# 2018_PanneauDomotiqueSimple.net
KiCad netlist of a schematic drawn in Altium Designer
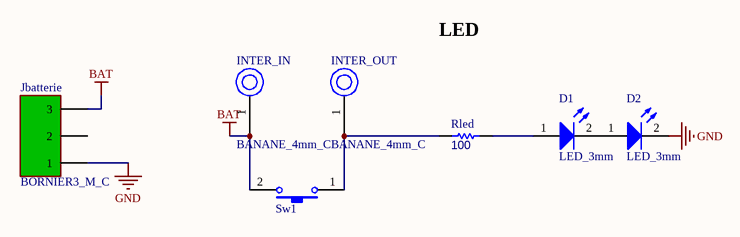
[diagram p0: 2018_PanneauDomotiqueSimple.SchDoc]

(export (version "E")
  (design (tool "Eeschema 10.0.6"))
  (components
    (comp (ref "D1")
      (value "LED_3MM")
      (footprint "LED_3MM")
      (description "LED 3MM - ROUGE/VERTE/JAUNE")
      (fields (field (name "TYPE") "LED_3mm"))
      (libsource (lib "affichage") (part "LED_3MM"))
    )
    (comp (ref "D2")
      (value "LED_3MM")
      (footprint "LED_3MM")
      (description "LED 3MM - ROUGE/VERTE/JAUNE")
      (fields (field (name "TYPE") "LED_3mm"))
      (libsource (lib "affichage") (part "LED_3MM"))
    )
    (comp (ref "INTER_IN")
      (value "DOUILLE BANANE 4mm COUDEE")
      (footprint "DOUILLE_BANANE_4MM_COUDEE")
      (description "DOUILLE BANANE 4 mm COUDEE")
      (fields (field (name "TYPE") "BANANE_4mm_C"))
      (libsource (lib "connecteurs") (part "DOUILLE_BANANE_4mm_COUDEE"))
    )
    (comp (ref "INTER_OUT")
      (value "DOUILLE BANANE 4mm COUDEE")
      (footprint "DOUILLE_BANANE_4MM_COUDEE")
      (description "DOUILLE BANANE 4 mm COUDEE")
      (fields (field (name "TYPE") "BANANE_4mm_C"))
      (libsource (lib "connecteurs") (part "DOUILLE_BANANE_4mm_COUDEE"))
    )
    (comp (ref "Jbatterie")
      (value "BORNIER3 MALE COUDE")
      (footprint "BORNIER3_M_C")
      (description "BORNIER 3 PLOTS MALE COUDE - ENFICHAGE PARALLELE")
      (fields (field (name "TYPE") "BORNIER3_M_C"))
      (libsource (lib "connecteurs") (part "BORNIER3_MALE_COUDE"))
    )
    (comp (ref "Rled")
      (value "100")
      (footprint "RESISTANCE_1/4W")
      (description "RESISTANCE TRAVERSANTE AXIALE 1/4W")
      (fields (field (name "Comment") "RESISTANCE_AXIALE_1/4W"))
      (libsource (lib "composants passifs") (part "RESISTANCE_AXIALE_1/4W"))
    )
    (comp (ref "Sw1")
      (value "BOUTON_POUSSOIR_MINIATURE_TRAVERSANT")
      (footprint "BOUTON_POUSSE_PLAT_6x6")
      (description "BOUTON POUSSOIR MINIATURE TRAVERSANT ON/OFF")
      (libsource (lib "commutation") (part "BOUTON_POUSSOIR_MINIATURE_TRAVERSANT"))
    )
  )
  (nets
    (net (code "1") (name "BAT") (class "Default")
      (node (ref "INTER_IN") (pin "1") (pinfunction "1_1") (pintype "passive"))
      (node (ref "Jbatterie") (pin "3") (pinfunction "3_3") (pintype "passive"))
      (node (ref "Sw1") (pin "2") (pinfunction "2_2") (pintype "passive"))
    )
    (net (code "2") (name "GND") (class "Default")
      (node (ref "D2") (pin "2") (pinfunction "2_2") (pintype "passive"))
      (node (ref "Jbatterie") (pin "1") (pinfunction "1_1") (pintype "passive"))
    )
    (net (code "3") (name "Net-(D1-Pad1)") (class "Default")
      (node (ref "D1") (pin "1") (pinfunction "1_1") (pintype "passive"))
      (node (ref "Rled") (pin "2") (pinfunction "2_2") (pintype "passive"))
    )
    (net (code "4") (name "Net-(D1-Pad2)") (class "Default")
      (node (ref "D1") (pin "2") (pinfunction "2_2") (pintype "passive"))
      (node (ref "D2") (pin "1") (pinfunction "1_1") (pintype "passive"))
    )
    (net (code "5") (name "Net-(INTER_OUT-Pad1)") (class "Default")
      (node (ref "INTER_OUT") (pin "1") (pinfunction "1_1") (pintype "passive"))
      (node (ref "Rled") (pin "1") (pinfunction "1_1") (pintype "passive"))
      (node (ref "Sw1") (pin "1") (pinfunction "1_1") (pintype "passive"))
    )
    (net (code "6") (name "unconnected-(Jbatterie-Pad2)") (class "Default")
      (node (ref "Jbatterie") (pin "2") (pinfunction "2_2") (pintype "passive"))
    )
  )
)
